# ESP32_breakout_v2_2.net
KiCad netlist of a schematic drawn in EAGLE
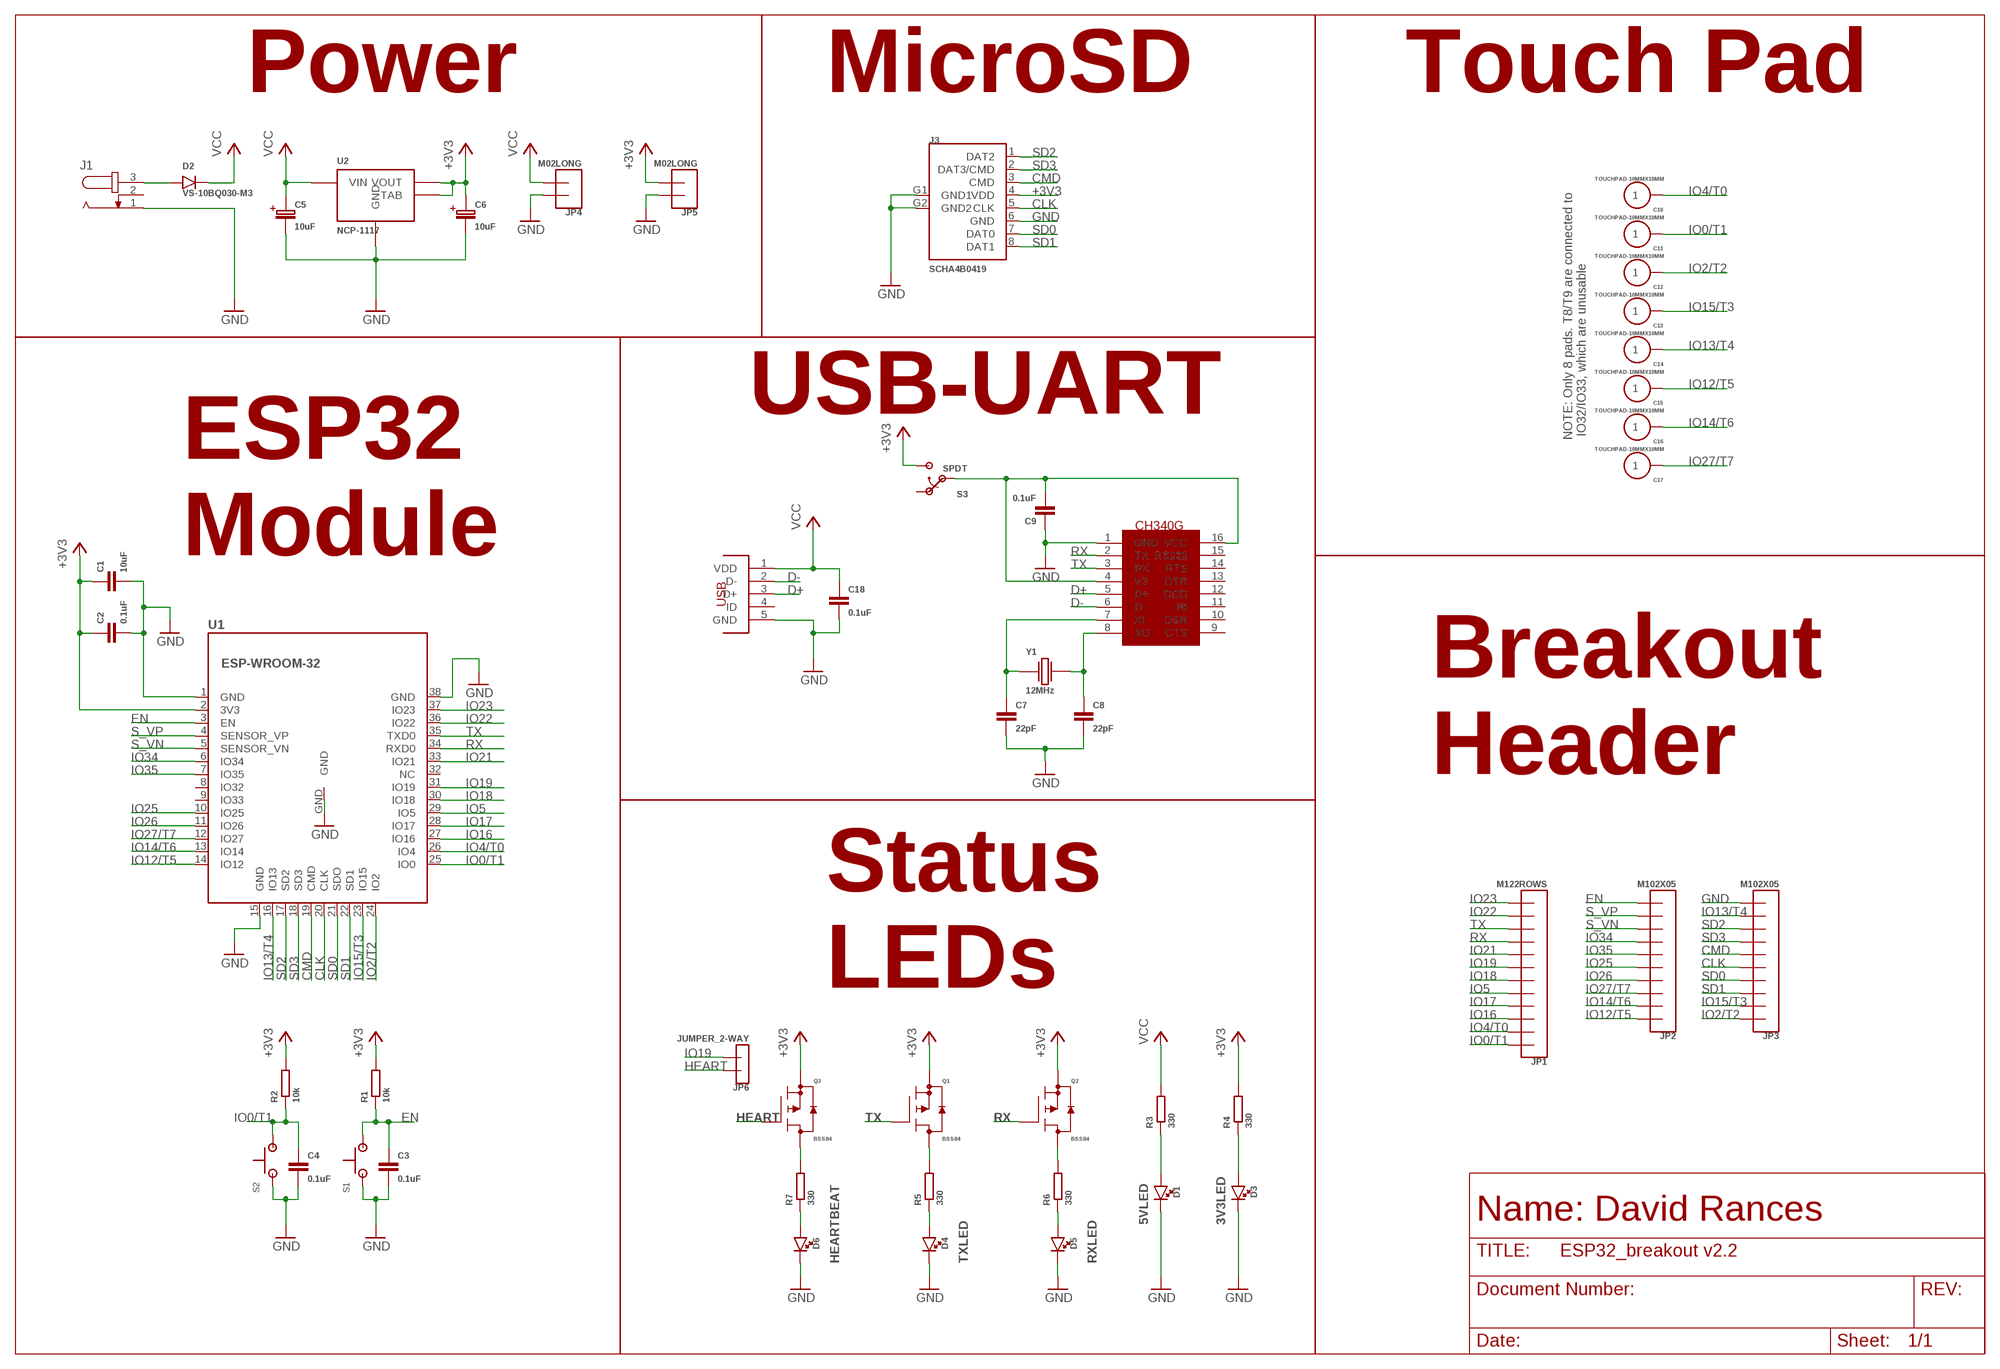
[diagram p0: schematic, sheet 1]

(export (version "E")
  (design (tool "Eeschema 10.0.6"))
  (components
    (comp (ref "C1")
      (value "10uF")
      (footprint "eagle-import:CAP-0603")
      (libsource (lib "eagle-import") (part "CAP0603"))
    )
    (comp (ref "C2")
      (value "0.1uF")
      (footprint "eagle-import:CAP-0603")
      (libsource (lib "eagle-import") (part "CAP0603"))
    )
    (comp (ref "C3")
      (value "0.1uF")
      (footprint "eagle-import:CAP-0603")
      (libsource (lib "eagle-import") (part "CAP0603"))
    )
    (comp (ref "C4")
      (value "0.1uF")
      (footprint "eagle-import:CAP-0603")
      (libsource (lib "eagle-import") (part "CAP0603"))
    )
    (comp (ref "C5")
      (value "10uF")
      (footprint "eagle-import:B-3528")
      (libsource (lib "eagle-import") (part "CAP-POLARCASEB-3528"))
    )
    (comp (ref "C6")
      (value "10uF")
      (footprint "eagle-import:B-3528")
      (libsource (lib "eagle-import") (part "CAP-POLARCASEB-3528"))
    )
    (comp (ref "C7")
      (value "22pF")
      (footprint "eagle-import:CAP-0603")
      (libsource (lib "eagle-import") (part "CAP0603"))
    )
    (comp (ref "C8")
      (value "22pF")
      (footprint "eagle-import:CAP-0603")
      (libsource (lib "eagle-import") (part "CAP0603"))
    )
    (comp (ref "C9")
      (value "0.1uF")
      (footprint "eagle-import:CAP-0603")
      (libsource (lib "eagle-import") (part "CAP0603"))
    )
    (comp (ref "C10")
      (value "TOUCHPAD-10MMX10MM")
      (footprint "eagle-import:TOUCH-10MMX10MM")
      (libsource (lib "eagle-import") (part "TOUCHPAD-10MMX10MM"))
    )
    (comp (ref "C11")
      (value "TOUCHPAD-10MMX10MM")
      (footprint "eagle-import:TOUCH-10MMX10MM")
      (libsource (lib "eagle-import") (part "TOUCHPAD-10MMX10MM"))
    )
    (comp (ref "C12")
      (value "TOUCHPAD-10MMX10MM")
      (footprint "eagle-import:TOUCH-10MMX10MM")
      (libsource (lib "eagle-import") (part "TOUCHPAD-10MMX10MM"))
    )
    (comp (ref "C13")
      (value "TOUCHPAD-10MMX10MM")
      (footprint "eagle-import:TOUCH-10MMX10MM")
      (libsource (lib "eagle-import") (part "TOUCHPAD-10MMX10MM"))
    )
    (comp (ref "C14")
      (value "TOUCHPAD-10MMX10MM")
      (footprint "eagle-import:TOUCH-10MMX10MM")
      (libsource (lib "eagle-import") (part "TOUCHPAD-10MMX10MM"))
    )
    (comp (ref "C15")
      (value "TOUCHPAD-10MMX10MM")
      (footprint "eagle-import:TOUCH-10MMX10MM")
      (libsource (lib "eagle-import") (part "TOUCHPAD-10MMX10MM"))
    )
    (comp (ref "C16")
      (value "TOUCHPAD-10MMX10MM")
      (footprint "eagle-import:TOUCH-10MMX10MM")
      (libsource (lib "eagle-import") (part "TOUCHPAD-10MMX10MM"))
    )
    (comp (ref "C17")
      (value "TOUCHPAD-10MMX10MM")
      (footprint "eagle-import:TOUCH-10MMX10MM")
      (libsource (lib "eagle-import") (part "TOUCHPAD-10MMX10MM"))
    )
    (comp (ref "C18")
      (value "0.1uF")
      (footprint "eagle-import:CAP-0603")
      (libsource (lib "eagle-import") (part "CAP0603"))
    )
    (comp (ref "D1")
      (value "LED1206")
      (footprint "eagle-import:LED-1206")
      (libsource (lib "eagle-import") (part "LED1206"))
    )
    (comp (ref "D2")
      (value "VS-10BQ030-M3")
      (footprint "eagle-import:DO-214AA")
      (libsource (lib "eagle-import") (part "VS-10BQ030-M3"))
    )
    (comp (ref "D3")
      (value "LED1206")
      (footprint "eagle-import:LED-1206")
      (libsource (lib "eagle-import") (part "LED1206"))
    )
    (comp (ref "D4")
      (value "LED1206")
      (footprint "eagle-import:LED-1206")
      (libsource (lib "eagle-import") (part "LED1206"))
    )
    (comp (ref "D5")
      (value "LED1206")
      (footprint "eagle-import:LED-1206")
      (libsource (lib "eagle-import") (part "LED1206"))
    )
    (comp (ref "D6")
      (value "LED1206")
      (footprint "eagle-import:LED-1206")
      (libsource (lib "eagle-import") (part "LED1206"))
    )
    (comp (ref "J1")
      (value "JACK-PLUG0")
      (footprint "eagle-import:SPC4077")
      (libsource (lib "eagle-import") (part "JACK-PLUG0"))
    )
    (comp (ref "J3")
      (value "SCHA4B0419")
      (footprint "eagle-import:MICROSD_SCHA4B0419")
      (libsource (lib "eagle-import") (part "SCHA4B0419"))
    )
    (comp (ref "JP1")
      (value "M122ROWS")
      (footprint "eagle-import:2X06")
      (libsource (lib "eagle-import") (part "M122ROWS"))
    )
    (comp (ref "JP2")
      (value "M102X05")
      (footprint "eagle-import:2X05")
      (libsource (lib "eagle-import") (part "M102X05"))
    )
    (comp (ref "JP3")
      (value "M102X05")
      (footprint "eagle-import:2X05")
      (libsource (lib "eagle-import") (part "M102X05"))
    )
    (comp (ref "JP4")
      (value "M02LONG")
      (footprint "eagle-import:1X02-LONG")
      (libsource (lib "eagle-import") (part "M02LONG"))
    )
    (comp (ref "JP5")
      (value "M02LONG")
      (footprint "eagle-import:1X02-LONG")
      (libsource (lib "eagle-import") (part "M02LONG"))
    )
    (comp (ref "JP6")
      (value "JUMPER_2-WAY")
      (footprint "eagle-import:1X02")
      (libsource (lib "eagle-import") (part "JUMPER_2-WAY"))
    )
    (comp (ref "Q1")
      (value "BSS84")
      (footprint "eagle-import:SOT-23-3")
      (libsource (lib "eagle-import") (part "BSS84"))
    )
    (comp (ref "Q2")
      (value "BSS84")
      (footprint "eagle-import:SOT-23-3")
      (libsource (lib "eagle-import") (part "BSS84"))
    )
    (comp (ref "Q3")
      (value "BSS84")
      (footprint "eagle-import:SOT-23-3")
      (libsource (lib "eagle-import") (part "BSS84"))
    )
    (comp (ref "R1")
      (value "10k")
      (footprint "eagle-import:RES-0603")
      (libsource (lib "eagle-import") (part "RESISTOR0603"))
    )
    (comp (ref "R2")
      (value "10k")
      (footprint "eagle-import:RES-0603")
      (libsource (lib "eagle-import") (part "RESISTOR0603"))
    )
    (comp (ref "R3")
      (value "330")
      (footprint "eagle-import:RES-0805")
      (libsource (lib "eagle-import") (part "RESISTOR0805"))
    )
    (comp (ref "R4")
      (value "330")
      (footprint "eagle-import:RES-0805")
      (libsource (lib "eagle-import") (part "RESISTOR0805"))
    )
    (comp (ref "R5")
      (value "330")
      (footprint "eagle-import:RES-0805")
      (libsource (lib "eagle-import") (part "RESISTOR0805"))
    )
    (comp (ref "R6")
      (value "330")
      (footprint "eagle-import:RES-0805")
      (libsource (lib "eagle-import") (part "RESISTOR0805"))
    )
    (comp (ref "R7")
      (value "330")
      (footprint "eagle-import:RES-0805")
      (libsource (lib "eagle-import") (part "RESISTOR0805"))
    )
    (comp (ref "S1")
      (value "PUSHBUTTONSKHMQME010")
      (footprint "eagle-import:SKHMQME010")
      (libsource (lib "eagle-import") (part "PUSHBUTTONSKHMQME010"))
    )
    (comp (ref "S2")
      (value "PUSHBUTTONSKHMQME010")
      (footprint "eagle-import:SKHMQME010")
      (libsource (lib "eagle-import") (part "PUSHBUTTONSKHMQME010"))
    )
    (comp (ref "S3")
      (value "SPDT")
      (footprint "eagle-import:1X03")
      (libsource (lib "eagle-import") (part "SPDT"))
    )
    (comp (ref "U$4")
      (value "MOLEX_USBMICRO")
      (footprint "eagle-import:MOLEX_47346-001")
      (libsource (lib "eagle-import") (part "MOLEX_USBMICRO"))
    )
    (comp (ref "U$7")
      (value "CH340G")
      (footprint "eagle-import:SOIC16")
      (libsource (lib "eagle-import") (part "CH340G"))
    )
    (comp (ref "U1")
      (value "ESP-WROOM-32")
      (footprint "eagle-import:ESP-WROOM-32")
      (libsource (lib "eagle-import") (part "ESP-WROOM-32"))
    )
    (comp (ref "U2")
      (value "NCP-1117")
      (footprint "eagle-import:SOT-223-4")
      (libsource (lib "eagle-import") (part "NCP-1117"))
    )
    (comp (ref "Y1")
      (value "12MHz")
      (footprint "eagle-import:HC-49_US")
      (libsource (lib "eagle-import") (part "ABLS-12MHZ-B2-T"))
    )
  )
  (nets
    (net (code "1") (name "+3V3") (class "Default")
      (node (ref "C1") (pin "1") (pinfunction "1_1") (pintype "passive"))
      (node (ref "C2") (pin "1") (pinfunction "1_1") (pintype "passive"))
      (node (ref "C6") (pin "P") (pinfunction "P_P") (pintype "passive"))
      (node (ref "J3") (pin "4") (pinfunction "VDD_4") (pintype "bidirectional"))
      (node (ref "JP5") (pin "2") (pinfunction "2_2") (pintype "bidirectional"))
      (node (ref "Q1") (pin "S") (pinfunction "S_S") (pintype "bidirectional"))
      (node (ref "Q2") (pin "S") (pinfunction "S_S") (pintype "bidirectional"))
      (node (ref "Q3") (pin "S") (pinfunction "S_S") (pintype "bidirectional"))
      (node (ref "R1") (pin "2") (pinfunction "2_2") (pintype "passive"))
      (node (ref "R2") (pin "2") (pinfunction "2_2") (pintype "passive"))
      (node (ref "R4") (pin "2") (pinfunction "2_2") (pintype "passive"))
      (node (ref "S3") (pin "3") (pinfunction "2_3") (pintype "bidirectional"))
      (node (ref "U1") (pin "2") (pinfunction "3V3_2") (pintype "bidirectional"))
      (node (ref "U2") (pin "2") (pinfunction "VOUT_2") (pintype "power_in"))
      (node (ref "U2") (pin "PAD") (pinfunction "TAB_PAD") (pintype "power_in"))
    )
    (net (code "2") (name "/CLK") (class "Default")
      (node (ref "J3") (pin "5") (pinfunction "CLK_5") (pintype "bidirectional"))
      (node (ref "JP3") (pin "5") (pinfunction "5_5") (pintype "bidirectional"))
      (node (ref "U1") (pin "20") (pinfunction "CLK_20") (pintype "bidirectional"))
    )
    (net (code "3") (name "/CMD") (class "Default")
      (node (ref "J3") (pin "3") (pinfunction "CMD_3") (pintype "bidirectional"))
      (node (ref "JP3") (pin "6") (pinfunction "6_6") (pintype "bidirectional"))
      (node (ref "U1") (pin "19") (pinfunction "CMD_19") (pintype "bidirectional"))
    )
    (net (code "4") (name "/D+") (class "Default")
      (node (ref "U$4") (pin "3") (pinfunction "D+_3") (pintype "bidirectional"))
      (node (ref "U$7") (pin "5") (pinfunction "D+_5") (pintype "bidirectional"))
    )
    (net (code "5") (name "/D-") (class "Default")
      (node (ref "U$4") (pin "2") (pinfunction "D-_2") (pintype "bidirectional"))
      (node (ref "U$7") (pin "6") (pinfunction "D-_6") (pintype "bidirectional"))
    )
    (net (code "6") (name "/EN") (class "Default")
      (node (ref "C3") (pin "1") (pinfunction "1_1") (pintype "passive"))
      (node (ref "JP2") (pin "10") (pinfunction "10_10") (pintype "bidirectional"))
      (node (ref "R1") (pin "1") (pinfunction "1_1") (pintype "passive"))
      (node (ref "S1") (pin "3") (pinfunction "2_3") (pintype "bidirectional"))
      (node (ref "S1") (pin "4") (pinfunction "2_4") (pintype "bidirectional"))
      (node (ref "U1") (pin "3") (pinfunction "EN_3") (pintype "bidirectional"))
    )
    (net (code "7") (name "/HEART") (class "Default")
      (node (ref "JP6") (pin "1") (pinfunction "1_1") (pintype "bidirectional"))
      (node (ref "Q3") (pin "G") (pinfunction "G_G") (pintype "bidirectional"))
    )
    (net (code "8") (name "/IO0{slash}T1") (class "Default")
      (node (ref "C11") (pin "P$1") (pinfunction "1_P$1") (pintype "bidirectional"))
      (node (ref "C4") (pin "1") (pinfunction "1_1") (pintype "passive"))
      (node (ref "JP1") (pin "1") (pinfunction "1_1") (pintype "bidirectional"))
      (node (ref "R2") (pin "1") (pinfunction "1_1") (pintype "passive"))
      (node (ref "S2") (pin "3") (pinfunction "2_3") (pintype "bidirectional"))
      (node (ref "S2") (pin "4") (pinfunction "2_4") (pintype "bidirectional"))
      (node (ref "U1") (pin "25") (pinfunction "IO0_25") (pintype "bidirectional"))
    )
    (net (code "9") (name "/IO2{slash}T2") (class "Default")
      (node (ref "C12") (pin "P$1") (pinfunction "1_P$1") (pintype "bidirectional"))
      (node (ref "JP3") (pin "1") (pinfunction "1_1") (pintype "bidirectional"))
      (node (ref "U1") (pin "24") (pinfunction "IO2_24") (pintype "bidirectional"))
    )
    (net (code "10") (name "/IO4{slash}T0") (class "Default")
      (node (ref "C10") (pin "P$1") (pinfunction "1_P$1") (pintype "bidirectional"))
      (node (ref "JP1") (pin "2") (pinfunction "2_2") (pintype "bidirectional"))
      (node (ref "U1") (pin "26") (pinfunction "IO4_26") (pintype "bidirectional"))
    )
    (net (code "11") (name "/IO5") (class "Default")
      (node (ref "JP1") (pin "5") (pinfunction "5_5") (pintype "bidirectional"))
      (node (ref "U1") (pin "29") (pinfunction "IO5_29") (pintype "bidirectional"))
    )
    (net (code "12") (name "/IO12{slash}T5") (class "Default")
      (node (ref "C15") (pin "P$1") (pinfunction "1_P$1") (pintype "bidirectional"))
      (node (ref "JP2") (pin "1") (pinfunction "1_1") (pintype "bidirectional"))
      (node (ref "U1") (pin "14") (pinfunction "IO12_14") (pintype "bidirectional"))
    )
    (net (code "13") (name "/IO13{slash}T4") (class "Default")
      (node (ref "C14") (pin "P$1") (pinfunction "1_P$1") (pintype "bidirectional"))
      (node (ref "JP3") (pin "9") (pinfunction "9_9") (pintype "bidirectional"))
      (node (ref "U1") (pin "16") (pinfunction "IO13_16") (pintype "bidirectional"))
    )
    (net (code "14") (name "/IO14{slash}T6") (class "Default")
      (node (ref "C16") (pin "P$1") (pinfunction "1_P$1") (pintype "bidirectional"))
      (node (ref "JP2") (pin "2") (pinfunction "2_2") (pintype "bidirectional"))
      (node (ref "U1") (pin "13") (pinfunction "IO14_13") (pintype "bidirectional"))
    )
    (net (code "15") (name "/IO15{slash}T3") (class "Default")
      (node (ref "C13") (pin "P$1") (pinfunction "1_P$1") (pintype "bidirectional"))
      (node (ref "JP3") (pin "2") (pinfunction "2_2") (pintype "bidirectional"))
      (node (ref "U1") (pin "23") (pinfunction "IO15_23") (pintype "bidirectional"))
    )
    (net (code "16") (name "/IO16") (class "Default")
      (node (ref "JP1") (pin "3") (pinfunction "3_3") (pintype "bidirectional"))
      (node (ref "U1") (pin "27") (pinfunction "IO16_27") (pintype "bidirectional"))
    )
    (net (code "17") (name "/IO17") (class "Default")
      (node (ref "JP1") (pin "4") (pinfunction "4_4") (pintype "bidirectional"))
      (node (ref "U1") (pin "28") (pinfunction "IO17_28") (pintype "bidirectional"))
    )
    (net (code "18") (name "/IO18") (class "Default")
      (node (ref "JP1") (pin "6") (pinfunction "6_6") (pintype "bidirectional"))
      (node (ref "U1") (pin "30") (pinfunction "IO18_30") (pintype "bidirectional"))
    )
    (net (code "19") (name "/IO19") (class "Default")
      (node (ref "JP1") (pin "7") (pinfunction "7_7") (pintype "bidirectional"))
      (node (ref "JP6") (pin "2") (pinfunction "2_2") (pintype "bidirectional"))
      (node (ref "U1") (pin "31") (pinfunction "IO19_31") (pintype "bidirectional"))
    )
    (net (code "20") (name "/IO21") (class "Default")
      (node (ref "JP1") (pin "8") (pinfunction "8_8") (pintype "bidirectional"))
      (node (ref "U1") (pin "33") (pinfunction "IO21_33") (pintype "bidirectional"))
    )
    (net (code "21") (name "/IO22") (class "Default")
      (node (ref "JP1") (pin "11") (pinfunction "11_11") (pintype "bidirectional"))
      (node (ref "U1") (pin "36") (pinfunction "IO22_36") (pintype "bidirectional"))
    )
    (net (code "22") (name "/IO23") (class "Default")
      (node (ref "JP1") (pin "12") (pinfunction "12_12") (pintype "bidirectional"))
      (node (ref "U1") (pin "37") (pinfunction "IO23_37") (pintype "bidirectional"))
    )
    (net (code "23") (name "/IO25") (class "Default")
      (node (ref "JP2") (pin "5") (pinfunction "5_5") (pintype "bidirectional"))
      (node (ref "U1") (pin "10") (pinfunction "IO25_10") (pintype "bidirectional"))
    )
    (net (code "24") (name "/IO26") (class "Default")
      (node (ref "JP2") (pin "4") (pinfunction "4_4") (pintype "bidirectional"))
      (node (ref "U1") (pin "11") (pinfunction "IO26_11") (pintype "bidirectional"))
    )
    (net (code "25") (name "/IO27{slash}T7") (class "Default")
      (node (ref "C17") (pin "P$1") (pinfunction "1_P$1") (pintype "bidirectional"))
      (node (ref "JP2") (pin "3") (pinfunction "3_3") (pintype "bidirectional"))
      (node (ref "U1") (pin "12") (pinfunction "IO27_12") (pintype "bidirectional"))
    )
    (net (code "26") (name "/IO34") (class "Default")
      (node (ref "JP2") (pin "7") (pinfunction "7_7") (pintype "bidirectional"))
      (node (ref "U1") (pin "6") (pinfunction "IO34_6") (pintype "bidirectional"))
    )
    (net (code "27") (name "/IO35") (class "Default")
      (node (ref "JP2") (pin "6") (pinfunction "6_6") (pintype "bidirectional"))
      (node (ref "U1") (pin "7") (pinfunction "IO35_7") (pintype "bidirectional"))
    )
    (net (code "28") (name "/RX") (class "Default")
      (node (ref "JP1") (pin "9") (pinfunction "9_9") (pintype "bidirectional"))
      (node (ref "Q2") (pin "G") (pinfunction "G_G") (pintype "bidirectional"))
      (node (ref "U$7") (pin "2") (pinfunction "TX_2") (pintype "bidirectional"))
      (node (ref "U1") (pin "34") (pinfunction "RXD0_34") (pintype "bidirectional"))
    )
    (net (code "29") (name "/SD0") (class "Default")
      (node (ref "J3") (pin "7") (pinfunction "DAT0_7") (pintype "bidirectional"))
      (node (ref "JP3") (pin "4") (pinfunction "4_4") (pintype "bidirectional"))
      (node (ref "U1") (pin "21") (pinfunction "SDO_21") (pintype "bidirectional"))
    )
    (net (code "30") (name "/SD1") (class "Default")
      (node (ref "J3") (pin "8") (pinfunction "DAT1_8") (pintype "bidirectional"))
      (node (ref "JP3") (pin "3") (pinfunction "3_3") (pintype "bidirectional"))
      (node (ref "U1") (pin "22") (pinfunction "SD1_22") (pintype "bidirectional"))
    )
    (net (code "31") (name "/SD2") (class "Default")
      (node (ref "J3") (pin "1") (pinfunction "DAT2_1") (pintype "bidirectional"))
      (node (ref "JP3") (pin "8") (pinfunction "8_8") (pintype "bidirectional"))
      (node (ref "U1") (pin "17") (pinfunction "SD2_17") (pintype "bidirectional"))
    )
    (net (code "32") (name "/SD3") (class "Default")
      (node (ref "J3") (pin "2") (pinfunction "DAT3/CMD_2") (pintype "bidirectional"))
      (node (ref "JP3") (pin "7") (pinfunction "7_7") (pintype "bidirectional"))
      (node (ref "U1") (pin "18") (pinfunction "SD3_18") (pintype "bidirectional"))
    )
    (net (code "33") (name "/S_VN") (class "Default")
      (node (ref "JP2") (pin "8") (pinfunction "8_8") (pintype "bidirectional"))
      (node (ref "U1") (pin "5") (pinfunction "SENSOR_VN_5") (pintype "bidirectional"))
    )
    (net (code "34") (name "/S_VP") (class "Default")
      (node (ref "JP2") (pin "9") (pinfunction "9_9") (pintype "bidirectional"))
      (node (ref "U1") (pin "4") (pinfunction "SENSOR_VP_4") (pintype "bidirectional"))
    )
    (net (code "35") (name "/TX") (class "Default")
      (node (ref "JP1") (pin "10") (pinfunction "10_10") (pintype "bidirectional"))
      (node (ref "Q1") (pin "G") (pinfunction "G_G") (pintype "bidirectional"))
      (node (ref "U$7") (pin "3") (pinfunction "RX_3") (pintype "bidirectional"))
      (node (ref "U1") (pin "35") (pinfunction "TXD0_35") (pintype "bidirectional"))
    )
    (net (code "36") (name "GND") (class "Default")
      (node (ref "C1") (pin "2") (pinfunction "2_2") (pintype "passive"))
      (node (ref "C18") (pin "2") (pinfunction "2_2") (pintype "passive"))
      (node (ref "C2") (pin "2") (pinfunction "2_2") (pintype "passive"))
      (node (ref "C3") (pin "2") (pinfunction "2_2") (pintype "passive"))
      (node (ref "C4") (pin "2") (pinfunction "2_2") (pintype "passive"))
      (node (ref "C5") (pin "N") (pinfunction "N_N") (pintype "passive"))
      (node (ref "C6") (pin "N") (pinfunction "N_N") (pintype "passive"))
      (node (ref "C7") (pin "2") (pinfunction "2_2") (pintype "passive"))
      (node (ref "C8") (pin "2") (pinfunction "2_2") (pintype "passive"))
      (node (ref "C9") (pin "1") (pinfunction "1_1") (pintype "passive"))
      (node (ref "D1") (pin "C") (pinfunction "C_C") (pintype "bidirectional"))
      (node (ref "D3") (pin "C") (pinfunction "C_C") (pintype "bidirectional"))
      (node (ref "D4") (pin "C") (pinfunction "C_C") (pintype "bidirectional"))
      (node (ref "D5") (pin "C") (pinfunction "C_C") (pintype "bidirectional"))
      (node (ref "D6") (pin "C") (pinfunction "C_C") (pintype "bidirectional"))
      (node (ref "J1") (pin "1") (pinfunction "1_1") (pintype "passive"))
      (node (ref "J3") (pin "6") (pinfunction "GND_6") (pintype "bidirectional"))
      (node (ref "J3") (pin "G1") (pinfunction "GND1_G1") (pintype "bidirectional"))
      (node (ref "J3") (pin "G2") (pinfunction "GND2_G2") (pintype "bidirectional"))
      (node (ref "JP3") (pin "10") (pinfunction "10_10") (pintype "bidirectional"))
      (node (ref "JP4") (pin "1") (pinfunction "1_1") (pintype "bidirectional"))
      (node (ref "JP5") (pin "1") (pinfunction "1_1") (pintype "bidirectional"))
      (node (ref "S1") (pin "1") (pinfunction "1_1") (pintype "bidirectional"))
      (node (ref "S1") (pin "2") (pinfunction "1_2") (pintype "bidirectional"))
      (node (ref "S2") (pin "1") (pinfunction "1_1") (pintype "bidirectional"))
      (node (ref "S2") (pin "2") (pinfunction "1_2") (pintype "bidirectional"))
      (node (ref "U$4") (pin "5") (pinfunction "GND_5") (pintype "bidirectional"))
      (node (ref "U$7") (pin "1") (pinfunction "GND_1") (pintype "bidirectional"))
      (node (ref "U1") (pin "1") (pinfunction "GND_1") (pintype "bidirectional"))
      (node (ref "U1") (pin "15") (pinfunction "GND_15") (pintype "bidirectional"))
      (node (ref "U1") (pin "38") (pinfunction "GND_38") (pintype "bidirectional"))
      (node (ref "U1") (pin "GND") (pinfunction "GND_GND") (pintype "bidirectional"))
      (node (ref "U2") (pin "1") (pinfunction "GND_1") (pintype "power_in"))
    )
    (net (code "37") (name "Net-(D1-PadA)") (class "Default")
      (node (ref "D1") (pin "A") (pinfunction "A_A") (pintype "bidirectional"))
      (node (ref "R3") (pin "1") (pinfunction "1_1") (pintype "passive"))
    )
    (net (code "38") (name "Net-(D2-PadA)") (class "Default")
      (node (ref "D2") (pin "A") (pinfunction "A_A") (pintype "bidirectional"))
      (node (ref "J1") (pin "3") (pinfunction "3_3") (pintype "passive"))
    )
    (net (code "39") (name "Net-(D3-PadA)") (class "Default")
      (node (ref "D3") (pin "A") (pinfunction "A_A") (pintype "bidirectional"))
      (node (ref "R4") (pin "1") (pinfunction "1_1") (pintype "passive"))
    )
    (net (code "40") (name "Net-(D4-PadA)") (class "Default")
      (node (ref "D4") (pin "A") (pinfunction "A_A") (pintype "bidirectional"))
      (node (ref "R5") (pin "1") (pinfunction "1_1") (pintype "passive"))
    )
    (net (code "41") (name "Net-(D5-PadA)") (class "Default")
      (node (ref "D5") (pin "A") (pinfunction "A_A") (pintype "bidirectional"))
      (node (ref "R6") (pin "1") (pinfunction "1_1") (pintype "passive"))
    )
    (net (code "42") (name "Net-(D6-PadA)") (class "Default")
      (node (ref "D6") (pin "A") (pinfunction "A_A") (pintype "bidirectional"))
      (node (ref "R7") (pin "1") (pinfunction "1_1") (pintype "passive"))
    )
    (net (code "43") (name "Net-(Q1-PadD)") (class "Default")
      (node (ref "Q1") (pin "D") (pinfunction "D_D") (pintype "bidirectional"))
      (node (ref "R5") (pin "2") (pinfunction "2_2") (pintype "passive"))
    )
    (net (code "44") (name "Net-(Q2-PadD)") (class "Default")
      (node (ref "Q2") (pin "D") (pinfunction "D_D") (pintype "bidirectional"))
      (node (ref "R6") (pin "2") (pinfunction "2_2") (pintype "passive"))
    )
    (net (code "45") (name "Net-(Q3-PadD)") (class "Default")
      (node (ref "Q3") (pin "D") (pinfunction "D_D") (pintype "bidirectional"))
      (node (ref "R7") (pin "2") (pinfunction "2_2") (pintype "passive"))
    )
    (net (code "46") (name "Net-(S3-OUT)") (class "Default")
      (node (ref "C9") (pin "2") (pinfunction "2_2") (pintype "passive"))
      (node (ref "S3") (pin "2") (pinfunction "OUT_2") (pintype "bidirectional"))
      (node (ref "U$7") (pin "16") (pinfunction "VCC_16") (pintype "bidirectional"))
      (node (ref "U$7") (pin "4") (pinfunction "V3_4") (pintype "bidirectional"))
    )
    (net (code "47") (name "Net-(U$7-XI)") (class "Default")
      (node (ref "C7") (pin "1") (pinfunction "1_1") (pintype "passive"))
      (node (ref "U$7") (pin "7") (pinfunction "XI_7") (pintype "bidirectional"))
      (node (ref "Y1") (pin "P$1") (pinfunction "1_P$1") (pintype "bidirectional"))
    )
    (net (code "48") (name "Net-(U$7-XO)") (class "Default")
      (node (ref "C8") (pin "1") (pinfunction "1_1") (pintype "passive"))
      (node (ref "U$7") (pin "8") (pinfunction "XO_8") (pintype "bidirectional"))
      (node (ref "Y1") (pin "P$2") (pinfunction "2_P$2") (pintype "bidirectional"))
    )
    (net (code "49") (name "VCC") (class "Default")
      (node (ref "C18") (pin "1") (pinfunction "1_1") (pintype "passive"))
      (node (ref "C5") (pin "P") (pinfunction "P_P") (pintype "passive"))
      (node (ref "D2") (pin "C") (pinfunction "C_C") (pintype "bidirectional"))
      (node (ref "JP4") (pin "2") (pinfunction "2_2") (pintype "bidirectional"))
      (node (ref "R3") (pin "2") (pinfunction "2_2") (pintype "passive"))
      (node (ref "U$4") (pin "1") (pinfunction "VDD_1") (pintype "bidirectional"))
      (node (ref "U2") (pin "3") (pinfunction "VIN_3") (pintype "power_in"))
    )
    (net (code "50") (name "unconnected-(J1-Pad2)") (class "Default")
      (node (ref "J1") (pin "2") (pinfunction "2_2") (pintype "passive"))
    )
    (net (code "51") (name "unconnected-(S1-3-Pad5)") (class "Default")
      (node (ref "S1") (pin "5") (pinfunction "3_5") (pintype "bidirectional"))
    )
    (net (code "52") (name "unconnected-(S2-3-Pad5)") (class "Default")
      (node (ref "S2") (pin "5") (pinfunction "3_5") (pintype "bidirectional"))
    )
    (net (code "53") (name "unconnected-(S3-Pad1)") (class "Default")
      (node (ref "S3") (pin "1") (pinfunction "1_1") (pintype "bidirectional"))
    )
    (net (code "54") (name "unconnected-(U$4-ID-Pad4)") (class "Default")
      (node (ref "U$4") (pin "4") (pinfunction "ID_4") (pintype "bidirectional"))
    )
    (net (code "55") (name "unconnected-(U$7-CTS-Pad9)") (class "Default")
      (node (ref "U$7") (pin "9") (pinfunction "CTS_9") (pintype "bidirectional"))
    )
    (net (code "56") (name "unconnected-(U$7-DCD-Pad12)") (class "Default")
      (node (ref "U$7") (pin "12") (pinfunction "DCD_12") (pintype "bidirectional"))
    )
    (net (code "57") (name "unconnected-(U$7-DSR-Pad10)") (class "Default")
      (node (ref "U$7") (pin "10") (pinfunction "DSR_10") (pintype "bidirectional"))
    )
    (net (code "58") (name "unconnected-(U$7-DTR-Pad13)") (class "Default")
      (node (ref "U$7") (pin "13") (pinfunction "DTR_13") (pintype "bidirectional"))
    )
    (net (code "59") (name "unconnected-(U$7-RI-Pad11)") (class "Default")
      (node (ref "U$7") (pin "11") (pinfunction "RI_11") (pintype "bidirectional"))
    )
    (net (code "60") (name "unconnected-(U$7-RS232-Pad15)") (class "Default")
      (node (ref "U$7") (pin "15") (pinfunction "RS232_15") (pintype "bidirectional"))
    )
    (net (code "61") (name "unconnected-(U$7-RTS-Pad14)") (class "Default")
      (node (ref "U$7") (pin "14") (pinfunction "RTS_14") (pintype "bidirectional"))
    )
    (net (code "62") (name "unconnected-(U1-IO32-Pad8)") (class "Default")
      (node (ref "U1") (pin "8") (pinfunction "IO32_8") (pintype "bidirectional"))
    )
    (net (code "63") (name "unconnected-(U1-IO33-Pad9)") (class "Default")
      (node (ref "U1") (pin "9") (pinfunction "IO33_9") (pintype "bidirectional"))
    )
    (net (code "64") (name "unconnected-(U1-NC-Pad32)") (class "Default")
      (node (ref "U1") (pin "32") (pinfunction "NC_32") (pintype "bidirectional"))
    )
  )
)
